# aafilter.net
KiCad netlist of a schematic drawn in Altium Designer
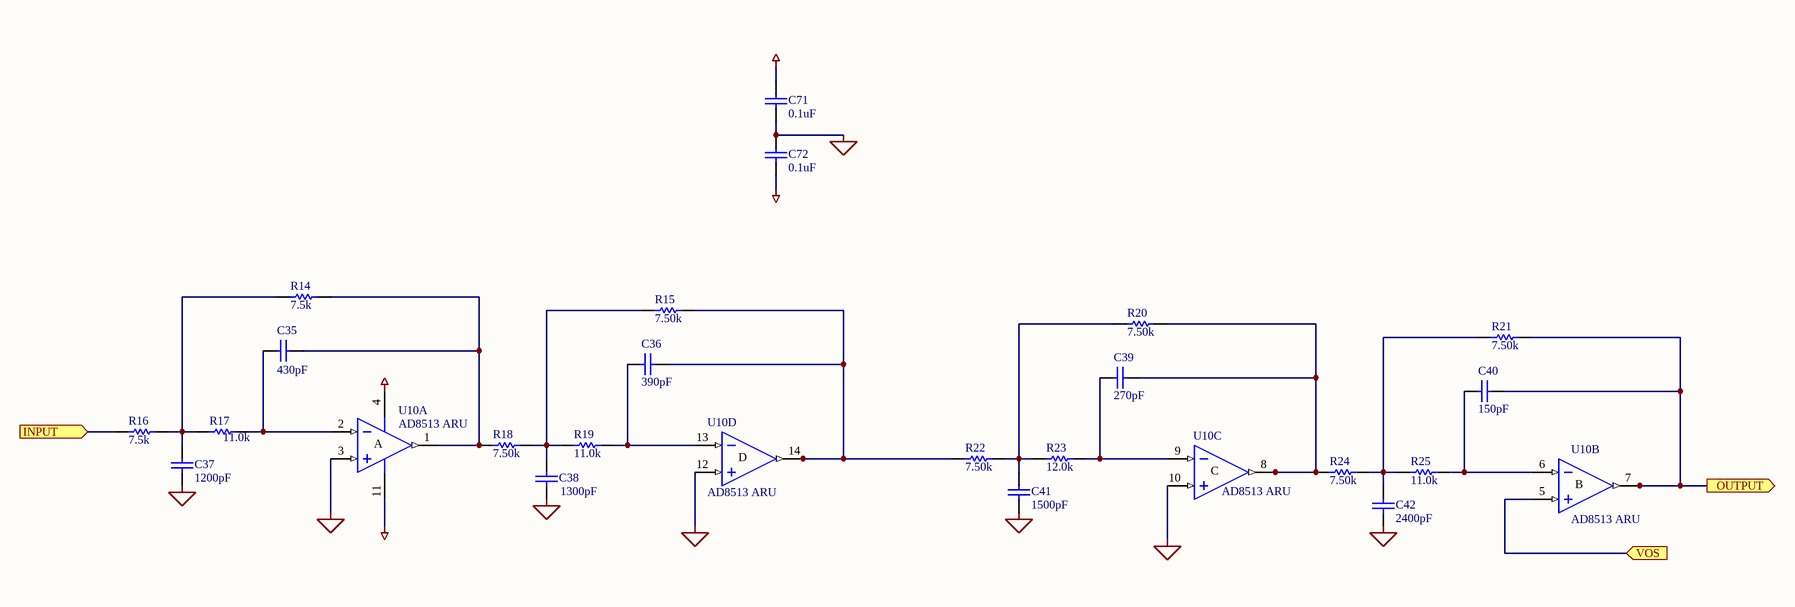
[diagram p0: aafilter.SCHDOC]

(export (version "E")
  (design (tool "Eeschema 10.0.6"))
  (components
    (comp (ref "C35")
      (value "430pF")
      (footprint "CC1608-0603")
      (description "Capacitor")
      (fields
        (field (name "MANUFACTURER") "Generic Components")
        (field (name "Comment") "Cap")
        (field (name "PUBLISHER") "Altium Limited")
      )
      (libsource (lib "Miscellaneous Devices") (part "Cap"))
    )
    (comp (ref "C36")
      (value "390pF")
      (footprint "CC1608-0603")
      (description "Capacitor")
      (fields
        (field (name "MANUFACTURER") "Generic Components")
        (field (name "Comment") "Cap")
        (field (name "PUBLISHER") "Altium Limited")
      )
      (libsource (lib "Miscellaneous Devices") (part "Cap"))
    )
    (comp (ref "C37")
      (value "1200pF")
      (footprint "CC1608-0603")
      (description "Capacitor")
      (fields
        (field (name "MANUFACTURER") "Generic Components")
        (field (name "Comment") "Cap")
        (field (name "PUBLISHER") "Altium Limited")
      )
      (libsource (lib "Miscellaneous Devices") (part "Cap"))
    )
    (comp (ref "C38")
      (value "1300pF")
      (footprint "CC1608-0603")
      (description "Capacitor")
      (fields
        (field (name "MANUFACTURER") "Generic Components")
        (field (name "Comment") "Cap")
        (field (name "PUBLISHER") "Altium Limited")
      )
      (libsource (lib "Miscellaneous Devices") (part "Cap"))
    )
    (comp (ref "C39")
      (value "270pF")
      (footprint "CC1608-0603")
      (description "Capacitor")
      (fields
        (field (name "MANUFACTURER") "Generic Components")
        (field (name "Comment") "Cap")
        (field (name "PUBLISHER") "Altium Limited")
      )
      (libsource (lib "Miscellaneous Devices") (part "Cap"))
    )
    (comp (ref "C40")
      (value "150pF")
      (footprint "CC1608-0603")
      (description "Capacitor")
      (fields
        (field (name "MANUFACTURER") "Generic Components")
        (field (name "Comment") "Cap")
        (field (name "PUBLISHER") "Altium Limited")
      )
      (libsource (lib "Miscellaneous Devices") (part "Cap"))
    )
    (comp (ref "C41")
      (value "1500pF")
      (footprint "CC1608-0603")
      (description "Capacitor")
      (fields
        (field (name "MANUFACTURER") "Generic Components")
        (field (name "Comment") "Cap")
        (field (name "PUBLISHER") "Altium Limited")
      )
      (libsource (lib "Miscellaneous Devices") (part "Cap"))
    )
    (comp (ref "C42")
      (value "2400pF")
      (footprint "CC1608-0603")
      (description "Capacitor")
      (fields
        (field (name "MANUFACTURER") "Generic Components")
        (field (name "Comment") "Cap")
        (field (name "PUBLISHER") "Altium Limited")
      )
      (libsource (lib "Miscellaneous Devices") (part "Cap"))
    )
    (comp (ref "C71")
      (value "0.1uF")
      (footprint "CC1608-0603")
      (description "Capacitor")
      (fields
        (field (name "MANUFACTURER") "Generic Components")
        (field (name "Comment") "Cap")
        (field (name "PUBLISHER") "Altium Limited")
      )
      (libsource (lib "Miscellaneous Devices") (part "Cap"))
    )
    (comp (ref "C72")
      (value "0.1uF")
      (footprint "CC1608-0603")
      (description "Capacitor")
      (fields
        (field (name "MANUFACTURER") "Generic Components")
        (field (name "Comment") "Cap")
        (field (name "PUBLISHER") "Altium Limited")
      )
      (libsource (lib "Miscellaneous Devices") (part "Cap"))
    )
    (comp (ref "R14")
      (value "7.5k")
      (footprint "CC1608-0603")
      (description "Resistor")
      (fields
        (field (name "MANUFACTURER") "Generic Components")
        (field (name "Comment") "Res1")
        (field (name "PUBLISHER") "Altium Limited")
      )
      (libsource (lib "Miscellaneous Devices") (part "Res1"))
    )
    (comp (ref "R15")
      (value "7.50k")
      (footprint "CC1608-0603")
      (description "Resistor")
      (fields
        (field (name "MANUFACTURER") "Generic Components")
        (field (name "Comment") "Res1")
        (field (name "PUBLISHER") "Altium Limited")
      )
      (libsource (lib "Miscellaneous Devices") (part "Res1"))
    )
    (comp (ref "R16")
      (value "7.5k")
      (footprint "CC1608-0603")
      (description "Resistor")
      (fields
        (field (name "MANUFACTURER") "Generic Components")
        (field (name "Comment") "Res1")
        (field (name "PUBLISHER") "Altium Limited")
      )
      (libsource (lib "Miscellaneous Devices") (part "Res1"))
    )
    (comp (ref "R17")
      (value "11.0k")
      (footprint "CC1608-0603")
      (description "Resistor")
      (fields
        (field (name "MANUFACTURER") "Generic Components")
        (field (name "Comment") "Res1")
        (field (name "PUBLISHER") "Altium Limited")
      )
      (libsource (lib "Miscellaneous Devices") (part "Res1"))
    )
    (comp (ref "R18")
      (value "7.50k")
      (footprint "CC1608-0603")
      (description "Resistor")
      (fields
        (field (name "MANUFACTURER") "Generic Components")
        (field (name "Comment") "Res1")
        (field (name "PUBLISHER") "Altium Limited")
      )
      (libsource (lib "Miscellaneous Devices") (part "Res1"))
    )
    (comp (ref "R19")
      (value "11.0k")
      (footprint "CC1608-0603")
      (description "Resistor")
      (fields
        (field (name "MANUFACTURER") "Generic Components")
        (field (name "Comment") "Res1")
        (field (name "PUBLISHER") "Altium Limited")
      )
      (libsource (lib "Miscellaneous Devices") (part "Res1"))
    )
    (comp (ref "R20")
      (value "7.50k")
      (footprint "CC1608-0603")
      (description "Resistor")
      (fields
        (field (name "MANUFACTURER") "Generic Components")
        (field (name "Comment") "Res1")
        (field (name "PUBLISHER") "Altium Limited")
      )
      (libsource (lib "Miscellaneous Devices") (part "Res1"))
    )
    (comp (ref "R21")
      (value "7.50k")
      (footprint "CC1608-0603")
      (description "Resistor")
      (fields
        (field (name "MANUFACTURER") "Generic Components")
        (field (name "Comment") "Res1")
        (field (name "PUBLISHER") "Altium Limited")
      )
      (libsource (lib "Miscellaneous Devices") (part "Res1"))
    )
    (comp (ref "R22")
      (value "7.50k")
      (footprint "CC1608-0603")
      (description "Resistor")
      (fields
        (field (name "MANUFACTURER") "Generic Components")
        (field (name "Comment") "Res1")
        (field (name "PUBLISHER") "Altium Limited")
      )
      (libsource (lib "Miscellaneous Devices") (part "Res1"))
    )
    (comp (ref "R23")
      (value "12.0k")
      (footprint "CC1608-0603")
      (description "Resistor")
      (fields
        (field (name "MANUFACTURER") "Generic Components")
        (field (name "Comment") "Res1")
        (field (name "PUBLISHER") "Altium Limited")
      )
      (libsource (lib "Miscellaneous Devices") (part "Res1"))
    )
    (comp (ref "R24")
      (value "7.50k")
      (footprint "CC1608-0603")
      (description "Resistor")
      (fields
        (field (name "MANUFACTURER") "Generic Components")
        (field (name "Comment") "Res1")
        (field (name "PUBLISHER") "Altium Limited")
      )
      (libsource (lib "Miscellaneous Devices") (part "Res1"))
    )
    (comp (ref "R25")
      (value "11.0k")
      (footprint "CC1608-0603")
      (description "Resistor")
      (fields
        (field (name "MANUFACTURER") "Generic Components")
        (field (name "Comment") "Res1")
        (field (name "PUBLISHER") "Altium Limited")
      )
      (libsource (lib "Miscellaneous Devices") (part "Res1"))
    )
    (comp (ref "U10")
      (value "AD8513 ARU")
      (footprint "SO-G14")
      (description "low-noise JFET quad OA")
      (libsource (lib "parts") (part "AD8513ARU"))
    )
  )
  (nets
    (net (code "1") (name "/INPUT") (class "Default")
      (node (ref "R16") (pin "1") (pinfunction "1_1") (pintype "passive"))
    )
    (net (code "2") (name "/OUTPUT") (class "Default")
      (node (ref "C40") (pin "1") (pinfunction "1_1") (pintype "passive"))
      (node (ref "R21") (pin "1") (pinfunction "1_1") (pintype "passive"))
      (node (ref "U10") (pin "7") (pinfunction "OUTB_7") (pintype "output"))
    )
    (net (code "3") (name "/VOS") (class "Default")
      (node (ref "U10") (pin "5") (pinfunction "IN+B_5") (pintype "input"))
    )
    (net (code "4") (name "AGND") (class "Default")
      (node (ref "C37") (pin "1") (pinfunction "1_1") (pintype "passive"))
      (node (ref "C38") (pin "1") (pinfunction "1_1") (pintype "passive"))
      (node (ref "C41") (pin "1") (pinfunction "1_1") (pintype "passive"))
      (node (ref "C42") (pin "1") (pinfunction "1_1") (pintype "passive"))
      (node (ref "C71") (pin "1") (pinfunction "1_1") (pintype "passive"))
      (node (ref "C72") (pin "2") (pinfunction "2_2") (pintype "passive"))
      (node (ref "U10") (pin "10") (pinfunction "IN+C_10") (pintype "input"))
      (node (ref "U10") (pin "12") (pinfunction "IN+D_12") (pintype "input"))
      (node (ref "U10") (pin "3") (pinfunction "IN+A_3") (pintype "input"))
    )
    (net (code "5") (name "AVDD") (class "Default")
      (node (ref "C71") (pin "2") (pinfunction "2_2") (pintype "passive"))
      (node (ref "U10") (pin "4") (pinfunction "V+_4") (pintype "power_in"))
    )
    (net (code "6") (name "AVSS") (class "Default")
      (node (ref "C72") (pin "1") (pinfunction "1_1") (pintype "passive"))
      (node (ref "U10") (pin "11") (pinfunction "V-_11") (pintype "power_in"))
    )
    (net (code "7") (name "Net-(C37-Pad2)") (class "Default")
      (node (ref "C37") (pin "2") (pinfunction "2_2") (pintype "passive"))
      (node (ref "R14") (pin "2") (pinfunction "2_2") (pintype "passive"))
      (node (ref "R16") (pin "2") (pinfunction "2_2") (pintype "passive"))
      (node (ref "R17") (pin "1") (pinfunction "1_1") (pintype "passive"))
    )
    (net (code "8") (name "Net-(C38-Pad2)") (class "Default")
      (node (ref "C38") (pin "2") (pinfunction "2_2") (pintype "passive"))
      (node (ref "R15") (pin "2") (pinfunction "2_2") (pintype "passive"))
      (node (ref "R18") (pin "2") (pinfunction "2_2") (pintype "passive"))
      (node (ref "R19") (pin "1") (pinfunction "1_1") (pintype "passive"))
    )
    (net (code "9") (name "Net-(C41-Pad2)") (class "Default")
      (node (ref "C41") (pin "2") (pinfunction "2_2") (pintype "passive"))
      (node (ref "R20") (pin "2") (pinfunction "2_2") (pintype "passive"))
      (node (ref "R22") (pin "2") (pinfunction "2_2") (pintype "passive"))
      (node (ref "R23") (pin "1") (pinfunction "1_1") (pintype "passive"))
    )
    (net (code "10") (name "Net-(C42-Pad2)") (class "Default")
      (node (ref "C42") (pin "2") (pinfunction "2_2") (pintype "passive"))
      (node (ref "R21") (pin "2") (pinfunction "2_2") (pintype "passive"))
      (node (ref "R24") (pin "2") (pinfunction "2_2") (pintype "passive"))
      (node (ref "R25") (pin "1") (pinfunction "1_1") (pintype "passive"))
    )
    (net (code "11") (name "Net-(U10A-IN-A)") (class "Default")
      (node (ref "C35") (pin "2") (pinfunction "2_2") (pintype "passive"))
      (node (ref "R17") (pin "2") (pinfunction "2_2") (pintype "passive"))
      (node (ref "U10") (pin "2") (pinfunction "IN-A_2") (pintype "input"))
    )
    (net (code "12") (name "Net-(U10A-OUTA)") (class "Default")
      (node (ref "C35") (pin "1") (pinfunction "1_1") (pintype "passive"))
      (node (ref "R14") (pin "1") (pinfunction "1_1") (pintype "passive"))
      (node (ref "R18") (pin "1") (pinfunction "1_1") (pintype "passive"))
      (node (ref "U10") (pin "1") (pinfunction "OUTA_1") (pintype "output"))
    )
    (net (code "13") (name "Net-(U10B-IN-B)") (class "Default")
      (node (ref "C40") (pin "2") (pinfunction "2_2") (pintype "passive"))
      (node (ref "R25") (pin "2") (pinfunction "2_2") (pintype "passive"))
      (node (ref "U10") (pin "6") (pinfunction "IN-B_6") (pintype "input"))
    )
    (net (code "14") (name "Net-(U10C-IN-C)") (class "Default")
      (node (ref "C39") (pin "2") (pinfunction "2_2") (pintype "passive"))
      (node (ref "R23") (pin "2") (pinfunction "2_2") (pintype "passive"))
      (node (ref "U10") (pin "9") (pinfunction "IN-C_9") (pintype "input"))
    )
    (net (code "15") (name "Net-(U10C-OUTC)") (class "Default")
      (node (ref "C39") (pin "1") (pinfunction "1_1") (pintype "passive"))
      (node (ref "R20") (pin "1") (pinfunction "1_1") (pintype "passive"))
      (node (ref "R24") (pin "1") (pinfunction "1_1") (pintype "passive"))
      (node (ref "U10") (pin "8") (pinfunction "OUTC_8") (pintype "output"))
    )
    (net (code "16") (name "Net-(U10D-IN-D)") (class "Default")
      (node (ref "C36") (pin "2") (pinfunction "2_2") (pintype "passive"))
      (node (ref "R19") (pin "2") (pinfunction "2_2") (pintype "passive"))
      (node (ref "U10") (pin "13") (pinfunction "IN-D_13") (pintype "input"))
    )
    (net (code "17") (name "Net-(U10D-OUTD)") (class "Default")
      (node (ref "C36") (pin "1") (pinfunction "1_1") (pintype "passive"))
      (node (ref "R15") (pin "1") (pinfunction "1_1") (pintype "passive"))
      (node (ref "R22") (pin "1") (pinfunction "1_1") (pintype "passive"))
      (node (ref "U10") (pin "14") (pinfunction "OUTD_14") (pintype "output"))
    )
  )
)
